# voltage_sensor.net
KiCad netlist of a schematic drawn in EAGLE
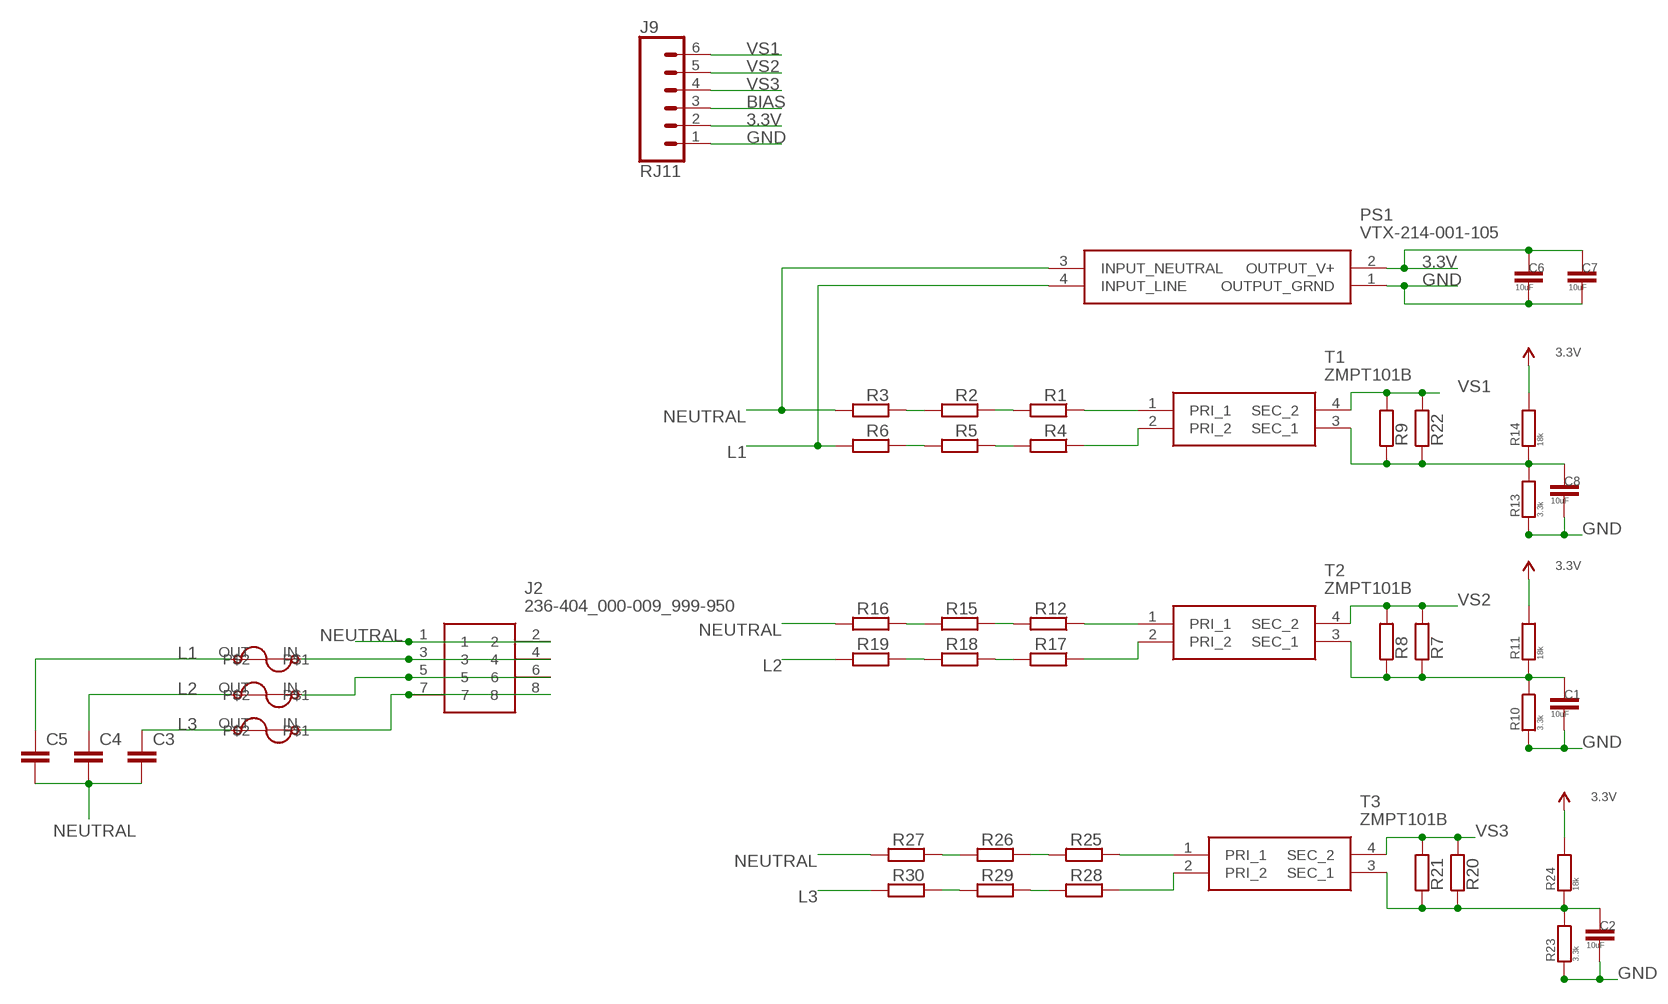
[diagram p0: schematic, sheet 1]

(export (version "E")
  (design (tool "Eeschema 10.0.6"))
  (components
    (comp (ref "C1")
      (value "10uF")
      (footprint "eagle-import:C0603")
      (libsource (lib "eagle-import") (part "C-EUC0603"))
    )
    (comp (ref "C2")
      (value "10uF")
      (footprint "eagle-import:C0603")
      (libsource (lib "eagle-import") (part "C-EUC0603"))
    )
    (comp (ref "C3")
      (value "C5/2.5")
      (footprint "eagle-import:C5B2.5")
      (libsource (lib "eagle-import") (part "C5/2.5"))
    )
    (comp (ref "C4")
      (value "C5/2.5")
      (footprint "eagle-import:C5B2.5")
      (libsource (lib "eagle-import") (part "C5/2.5"))
    )
    (comp (ref "C5")
      (value "C5/2.5")
      (footprint "eagle-import:C5B2.5")
      (libsource (lib "eagle-import") (part "C5/2.5"))
    )
    (comp (ref "C6")
      (value "10uF")
      (footprint "eagle-import:C0603")
      (libsource (lib "eagle-import") (part "C-EUC0603"))
    )
    (comp (ref "C7")
      (value "10uF")
      (footprint "eagle-import:C0603")
      (libsource (lib "eagle-import") (part "C-EUC0603"))
    )
    (comp (ref "C8")
      (value "10uF")
      (footprint "eagle-import:C0603")
      (libsource (lib "eagle-import") (part "C-EUC0603"))
    )
    (comp (ref "F1")
      (value "BEL1AFUSE")
      (footprint "eagle-import:BELFUSE1A")
      (libsource (lib "eagle-import") (part "BEL1AFUSE"))
    )
    (comp (ref "F2")
      (value "BEL1AFUSE")
      (footprint "eagle-import:BELFUSE1A")
      (libsource (lib "eagle-import") (part "BEL1AFUSE"))
    )
    (comp (ref "F3")
      (value "BEL1AFUSE")
      (footprint "eagle-import:BELFUSE1A")
      (libsource (lib "eagle-import") (part "BEL1AFUSE"))
    )
    (comp (ref "J2")
      (value "236-404_000-009_999-950")
      (footprint "eagle-import:236404000009999950")
      (fields (field (name "ARROW_PART_NUMBER") "236-404/000-009/999-950"))
      (libsource (lib "eagle-import") (part "236-404_000-009_999-950"))
    )
    (comp (ref "J9")
      (value "RJ11")
      (footprint "eagle-import:RJ11-6")
      (libsource (lib "eagle-import") (part "RJ11-6"))
    )
    (comp (ref "PS1")
      (value "VTX-214-001-105")
      (footprint "eagle-import:VTX214001105")
      (libsource (lib "eagle-import") (part "VTX-214-001-105"))
    )
    (comp (ref "R1")
      (value "R-EU_R1206")
      (footprint "eagle-import:R1206")
      (libsource (lib "eagle-import") (part "R-EU_R1206"))
    )
    (comp (ref "R2")
      (value "R-EU_R1206")
      (footprint "eagle-import:R1206")
      (libsource (lib "eagle-import") (part "R-EU_R1206"))
    )
    (comp (ref "R3")
      (value "R-EU_R1206")
      (footprint "eagle-import:R1206")
      (libsource (lib "eagle-import") (part "R-EU_R1206"))
    )
    (comp (ref "R4")
      (value "R-EU_R1206")
      (footprint "eagle-import:R1206")
      (libsource (lib "eagle-import") (part "R-EU_R1206"))
    )
    (comp (ref "R5")
      (value "R-EU_R1206")
      (footprint "eagle-import:R1206")
      (libsource (lib "eagle-import") (part "R-EU_R1206"))
    )
    (comp (ref "R6")
      (value "R-EU_R1206")
      (footprint "eagle-import:R1206")
      (libsource (lib "eagle-import") (part "R-EU_R1206"))
    )
    (comp (ref "R7")
      (value "R-EU_0204/7")
      (footprint "eagle-import:0204_7")
      (libsource (lib "eagle-import") (part "R-EU_0204/7"))
    )
    (comp (ref "R8")
      (value "R-EU_R1206")
      (footprint "eagle-import:R1206")
      (libsource (lib "eagle-import") (part "R-EU_R1206"))
    )
    (comp (ref "R9")
      (value "R-EU_R1206")
      (footprint "eagle-import:R1206")
      (libsource (lib "eagle-import") (part "R-EU_R1206"))
    )
    (comp (ref "R10")
      (value "3.3k")
      (footprint "eagle-import:R0603")
      (libsource (lib "eagle-import") (part "R-EU_R0603"))
    )
    (comp (ref "R11")
      (value "18k")
      (footprint "eagle-import:R0603")
      (libsource (lib "eagle-import") (part "R-EU_R0603"))
    )
    (comp (ref "R12")
      (value "R-EU_R1206")
      (footprint "eagle-import:R1206")
      (libsource (lib "eagle-import") (part "R-EU_R1206"))
    )
    (comp (ref "R13")
      (value "3.3k")
      (footprint "eagle-import:R0603")
      (libsource (lib "eagle-import") (part "R-EU_R0603"))
    )
    (comp (ref "R14")
      (value "18k")
      (footprint "eagle-import:R0603")
      (libsource (lib "eagle-import") (part "R-EU_R0603"))
    )
    (comp (ref "R15")
      (value "R-EU_R1206")
      (footprint "eagle-import:R1206")
      (libsource (lib "eagle-import") (part "R-EU_R1206"))
    )
    (comp (ref "R16")
      (value "R-EU_R1206")
      (footprint "eagle-import:R1206")
      (libsource (lib "eagle-import") (part "R-EU_R1206"))
    )
    (comp (ref "R17")
      (value "R-EU_R1206")
      (footprint "eagle-import:R1206")
      (libsource (lib "eagle-import") (part "R-EU_R1206"))
    )
    (comp (ref "R18")
      (value "R-EU_R1206")
      (footprint "eagle-import:R1206")
      (libsource (lib "eagle-import") (part "R-EU_R1206"))
    )
    (comp (ref "R19")
      (value "R-EU_R1206")
      (footprint "eagle-import:R1206")
      (libsource (lib "eagle-import") (part "R-EU_R1206"))
    )
    (comp (ref "R20")
      (value "R-EU_0204/7")
      (footprint "eagle-import:0204_7")
      (libsource (lib "eagle-import") (part "R-EU_0204/7"))
    )
    (comp (ref "R21")
      (value "R-EU_R1206")
      (footprint "eagle-import:R1206")
      (libsource (lib "eagle-import") (part "R-EU_R1206"))
    )
    (comp (ref "R22")
      (value "R-EU_0204/7")
      (footprint "eagle-import:0204_7")
      (libsource (lib "eagle-import") (part "R-EU_0204/7"))
    )
    (comp (ref "R23")
      (value "3.3k")
      (footprint "eagle-import:R0603")
      (libsource (lib "eagle-import") (part "R-EU_R0603"))
    )
    (comp (ref "R24")
      (value "18k")
      (footprint "eagle-import:R0603")
      (libsource (lib "eagle-import") (part "R-EU_R0603"))
    )
    (comp (ref "R25")
      (value "R-EU_R1206")
      (footprint "eagle-import:R1206")
      (libsource (lib "eagle-import") (part "R-EU_R1206"))
    )
    (comp (ref "R26")
      (value "R-EU_R1206")
      (footprint "eagle-import:R1206")
      (libsource (lib "eagle-import") (part "R-EU_R1206"))
    )
    (comp (ref "R27")
      (value "R-EU_R1206")
      (footprint "eagle-import:R1206")
      (libsource (lib "eagle-import") (part "R-EU_R1206"))
    )
    (comp (ref "R28")
      (value "R-EU_R1206")
      (footprint "eagle-import:R1206")
      (libsource (lib "eagle-import") (part "R-EU_R1206"))
    )
    (comp (ref "R29")
      (value "R-EU_R1206")
      (footprint "eagle-import:R1206")
      (libsource (lib "eagle-import") (part "R-EU_R1206"))
    )
    (comp (ref "R30")
      (value "R-EU_R1206")
      (footprint "eagle-import:R1206")
      (libsource (lib "eagle-import") (part "R-EU_R1206"))
    )
    (comp (ref "T1")
      (value "ZMPT101B")
      (footprint "eagle-import:ZMPT101B")
      (libsource (lib "eagle-import") (part "ZMPT101B"))
    )
    (comp (ref "T2")
      (value "ZMPT101B")
      (footprint "eagle-import:ZMPT101B")
      (libsource (lib "eagle-import") (part "ZMPT101B"))
    )
    (comp (ref "T3")
      (value "ZMPT101B")
      (footprint "eagle-import:ZMPT101B")
      (libsource (lib "eagle-import") (part "ZMPT101B"))
    )
  )
  (nets
    (net (code "1") (name "/BIAS") (class "Default")
      (node (ref "J9") (pin "3") (pinfunction "3_3") (pintype "passive"))
    )
    (net (code "2") (name "/GND") (class "Default")
      (node (ref "C1") (pin "2") (pinfunction "2_2") (pintype "passive"))
      (node (ref "C2") (pin "2") (pinfunction "2_2") (pintype "passive"))
      (node (ref "C6") (pin "2") (pinfunction "2_2") (pintype "passive"))
      (node (ref "C7") (pin "2") (pinfunction "2_2") (pintype "passive"))
      (node (ref "C8") (pin "2") (pinfunction "2_2") (pintype "passive"))
      (node (ref "J9") (pin "1") (pinfunction "1_1") (pintype "passive"))
      (node (ref "PS1") (pin "1") (pinfunction "OUTPUT_GRND_1") (pintype "bidirectional"))
      (node (ref "R10") (pin "2") (pinfunction "2_2") (pintype "passive"))
      (node (ref "R13") (pin "2") (pinfunction "2_2") (pintype "passive"))
      (node (ref "R23") (pin "2") (pinfunction "2_2") (pintype "passive"))
    )
    (net (code "3") (name "/L1") (class "Default")
      (node (ref "C5") (pin "1") (pinfunction "1_1") (pintype "passive"))
      (node (ref "F1") (pin "OUT") (pinfunction "P$1_OUT") (pintype "bidirectional"))
      (node (ref "PS1") (pin "4") (pinfunction "INPUT_LINE_4") (pintype "bidirectional"))
      (node (ref "R6") (pin "2") (pinfunction "2_2") (pintype "passive"))
    )
    (net (code "4") (name "/L2") (class "Default")
      (node (ref "C4") (pin "1") (pinfunction "1_1") (pintype "passive"))
      (node (ref "F2") (pin "OUT") (pinfunction "P$1_OUT") (pintype "bidirectional"))
      (node (ref "R19") (pin "2") (pinfunction "2_2") (pintype "passive"))
    )
    (net (code "5") (name "/L3") (class "Default")
      (node (ref "C3") (pin "1") (pinfunction "1_1") (pintype "passive"))
      (node (ref "F3") (pin "OUT") (pinfunction "P$1_OUT") (pintype "bidirectional"))
      (node (ref "R30") (pin "2") (pinfunction "2_2") (pintype "passive"))
    )
    (net (code "6") (name "/NEUTRAL") (class "Default")
      (node (ref "C3") (pin "2") (pinfunction "2_2") (pintype "passive"))
      (node (ref "C4") (pin "2") (pinfunction "2_2") (pintype "passive"))
      (node (ref "C5") (pin "2") (pinfunction "2_2") (pintype "passive"))
      (node (ref "J2") (pin "1") (pinfunction "1_1") (pintype "bidirectional"))
      (node (ref "J2") (pin "2") (pinfunction "2_2") (pintype "bidirectional"))
      (node (ref "PS1") (pin "3") (pinfunction "INPUT_NEUTRAL_3") (pintype "bidirectional"))
      (node (ref "R16") (pin "2") (pinfunction "2_2") (pintype "passive"))
      (node (ref "R27") (pin "2") (pinfunction "2_2") (pintype "passive"))
      (node (ref "R3") (pin "2") (pinfunction "2_2") (pintype "passive"))
    )
    (net (code "7") (name "/VS1") (class "Default")
      (node (ref "J9") (pin "6") (pinfunction "6_6") (pintype "passive"))
      (node (ref "R22") (pin "2") (pinfunction "2_2") (pintype "passive"))
      (node (ref "R9") (pin "2") (pinfunction "2_2") (pintype "passive"))
      (node (ref "T1") (pin "4") (pinfunction "SEC_2_4") (pintype "bidirectional"))
    )
    (net (code "8") (name "/VS2") (class "Default")
      (node (ref "J9") (pin "5") (pinfunction "5_5") (pintype "passive"))
      (node (ref "R7") (pin "2") (pinfunction "2_2") (pintype "passive"))
      (node (ref "R8") (pin "2") (pinfunction "2_2") (pintype "passive"))
      (node (ref "T2") (pin "4") (pinfunction "SEC_2_4") (pintype "bidirectional"))
    )
    (net (code "9") (name "/VS3") (class "Default")
      (node (ref "J9") (pin "4") (pinfunction "4_4") (pintype "passive"))
      (node (ref "R20") (pin "2") (pinfunction "2_2") (pintype "passive"))
      (node (ref "R21") (pin "2") (pinfunction "2_2") (pintype "passive"))
      (node (ref "T3") (pin "4") (pinfunction "SEC_2_4") (pintype "bidirectional"))
    )
    (net (code "10") (name "3.3V") (class "Default")
      (node (ref "C6") (pin "1") (pinfunction "1_1") (pintype "passive"))
      (node (ref "C7") (pin "1") (pinfunction "1_1") (pintype "passive"))
      (node (ref "J9") (pin "2") (pinfunction "2_2") (pintype "passive"))
      (node (ref "PS1") (pin "2") (pinfunction "OUTPUT_V+_2") (pintype "bidirectional"))
      (node (ref "R11") (pin "2") (pinfunction "2_2") (pintype "passive"))
      (node (ref "R14") (pin "2") (pinfunction "2_2") (pintype "passive"))
      (node (ref "R24") (pin "2") (pinfunction "2_2") (pintype "passive"))
    )
    (net (code "11") (name "Net-(F1-P$2)") (class "Default")
      (node (ref "F1") (pin "IN") (pinfunction "P$2_IN") (pintype "bidirectional"))
      (node (ref "J2") (pin "3") (pinfunction "3_3") (pintype "bidirectional"))
      (node (ref "J2") (pin "4") (pinfunction "4_4") (pintype "bidirectional"))
    )
    (net (code "12") (name "Net-(F2-P$2)") (class "Default")
      (node (ref "F2") (pin "IN") (pinfunction "P$2_IN") (pintype "bidirectional"))
      (node (ref "J2") (pin "5") (pinfunction "5_5") (pintype "bidirectional"))
      (node (ref "J2") (pin "6") (pinfunction "6_6") (pintype "bidirectional"))
    )
    (net (code "13") (name "Net-(F3-P$2)") (class "Default")
      (node (ref "F3") (pin "IN") (pinfunction "P$2_IN") (pintype "bidirectional"))
      (node (ref "J2") (pin "7") (pinfunction "7_7") (pintype "bidirectional"))
      (node (ref "J2") (pin "8") (pinfunction "8_8") (pintype "bidirectional"))
    )
    (net (code "14") (name "Net-(R1-Pad2)") (class "Default")
      (node (ref "R1") (pin "2") (pinfunction "2_2") (pintype "passive"))
      (node (ref "R2") (pin "1") (pinfunction "1_1") (pintype "passive"))
    )
    (net (code "15") (name "Net-(R2-Pad2)") (class "Default")
      (node (ref "R2") (pin "2") (pinfunction "2_2") (pintype "passive"))
      (node (ref "R3") (pin "1") (pinfunction "1_1") (pintype "passive"))
    )
    (net (code "16") (name "Net-(R4-Pad2)") (class "Default")
      (node (ref "R4") (pin "2") (pinfunction "2_2") (pintype "passive"))
      (node (ref "R5") (pin "1") (pinfunction "1_1") (pintype "passive"))
    )
    (net (code "17") (name "Net-(R5-Pad2)") (class "Default")
      (node (ref "R5") (pin "2") (pinfunction "2_2") (pintype "passive"))
      (node (ref "R6") (pin "1") (pinfunction "1_1") (pintype "passive"))
    )
    (net (code "18") (name "Net-(R12-Pad2)") (class "Default")
      (node (ref "R12") (pin "2") (pinfunction "2_2") (pintype "passive"))
      (node (ref "R15") (pin "1") (pinfunction "1_1") (pintype "passive"))
    )
    (net (code "19") (name "Net-(R15-Pad2)") (class "Default")
      (node (ref "R15") (pin "2") (pinfunction "2_2") (pintype "passive"))
      (node (ref "R16") (pin "1") (pinfunction "1_1") (pintype "passive"))
    )
    (net (code "20") (name "Net-(R17-Pad2)") (class "Default")
      (node (ref "R17") (pin "2") (pinfunction "2_2") (pintype "passive"))
      (node (ref "R18") (pin "1") (pinfunction "1_1") (pintype "passive"))
    )
    (net (code "21") (name "Net-(R18-Pad2)") (class "Default")
      (node (ref "R18") (pin "2") (pinfunction "2_2") (pintype "passive"))
      (node (ref "R19") (pin "1") (pinfunction "1_1") (pintype "passive"))
    )
    (net (code "22") (name "Net-(R25-Pad2)") (class "Default")
      (node (ref "R25") (pin "2") (pinfunction "2_2") (pintype "passive"))
      (node (ref "R26") (pin "1") (pinfunction "1_1") (pintype "passive"))
    )
    (net (code "23") (name "Net-(R26-Pad2)") (class "Default")
      (node (ref "R26") (pin "2") (pinfunction "2_2") (pintype "passive"))
      (node (ref "R27") (pin "1") (pinfunction "1_1") (pintype "passive"))
    )
    (net (code "24") (name "Net-(R28-Pad2)") (class "Default")
      (node (ref "R28") (pin "2") (pinfunction "2_2") (pintype "passive"))
      (node (ref "R29") (pin "1") (pinfunction "1_1") (pintype "passive"))
    )
    (net (code "25") (name "Net-(R29-Pad2)") (class "Default")
      (node (ref "R29") (pin "2") (pinfunction "2_2") (pintype "passive"))
      (node (ref "R30") (pin "1") (pinfunction "1_1") (pintype "passive"))
    )
    (net (code "26") (name "Net-(T1-PRI_1)") (class "Default")
      (node (ref "R1") (pin "1") (pinfunction "1_1") (pintype "passive"))
      (node (ref "T1") (pin "1") (pinfunction "PRI_1_1") (pintype "bidirectional"))
    )
    (net (code "27") (name "Net-(T1-PRI_2)") (class "Default")
      (node (ref "R4") (pin "1") (pinfunction "1_1") (pintype "passive"))
      (node (ref "T1") (pin "2") (pinfunction "PRI_2_2") (pintype "bidirectional"))
    )
    (net (code "28") (name "Net-(T1-SEC_1)") (class "Default")
      (node (ref "C8") (pin "1") (pinfunction "1_1") (pintype "passive"))
      (node (ref "R13") (pin "1") (pinfunction "1_1") (pintype "passive"))
      (node (ref "R14") (pin "1") (pinfunction "1_1") (pintype "passive"))
      (node (ref "R22") (pin "1") (pinfunction "1_1") (pintype "passive"))
      (node (ref "R9") (pin "1") (pinfunction "1_1") (pintype "passive"))
      (node (ref "T1") (pin "3") (pinfunction "SEC_1_3") (pintype "bidirectional"))
    )
    (net (code "29") (name "Net-(T2-PRI_1)") (class "Default")
      (node (ref "R12") (pin "1") (pinfunction "1_1") (pintype "passive"))
      (node (ref "T2") (pin "1") (pinfunction "PRI_1_1") (pintype "bidirectional"))
    )
    (net (code "30") (name "Net-(T2-PRI_2)") (class "Default")
      (node (ref "R17") (pin "1") (pinfunction "1_1") (pintype "passive"))
      (node (ref "T2") (pin "2") (pinfunction "PRI_2_2") (pintype "bidirectional"))
    )
    (net (code "31") (name "Net-(T2-SEC_1)") (class "Default")
      (node (ref "C1") (pin "1") (pinfunction "1_1") (pintype "passive"))
      (node (ref "R10") (pin "1") (pinfunction "1_1") (pintype "passive"))
      (node (ref "R11") (pin "1") (pinfunction "1_1") (pintype "passive"))
      (node (ref "R7") (pin "1") (pinfunction "1_1") (pintype "passive"))
      (node (ref "R8") (pin "1") (pinfunction "1_1") (pintype "passive"))
      (node (ref "T2") (pin "3") (pinfunction "SEC_1_3") (pintype "bidirectional"))
    )
    (net (code "32") (name "Net-(T3-PRI_1)") (class "Default")
      (node (ref "R25") (pin "1") (pinfunction "1_1") (pintype "passive"))
      (node (ref "T3") (pin "1") (pinfunction "PRI_1_1") (pintype "bidirectional"))
    )
    (net (code "33") (name "Net-(T3-PRI_2)") (class "Default")
      (node (ref "R28") (pin "1") (pinfunction "1_1") (pintype "passive"))
      (node (ref "T3") (pin "2") (pinfunction "PRI_2_2") (pintype "bidirectional"))
    )
    (net (code "34") (name "Net-(T3-SEC_1)") (class "Default")
      (node (ref "C2") (pin "1") (pinfunction "1_1") (pintype "passive"))
      (node (ref "R20") (pin "1") (pinfunction "1_1") (pintype "passive"))
      (node (ref "R21") (pin "1") (pinfunction "1_1") (pintype "passive"))
      (node (ref "R23") (pin "1") (pinfunction "1_1") (pintype "passive"))
      (node (ref "R24") (pin "1") (pinfunction "1_1") (pintype "passive"))
      (node (ref "T3") (pin "3") (pinfunction "SEC_1_3") (pintype "bidirectional"))
    )
  )
)
